# STM32F030_-_VGA_bare_-_v6.net
KiCad netlist of a schematic drawn in EAGLE
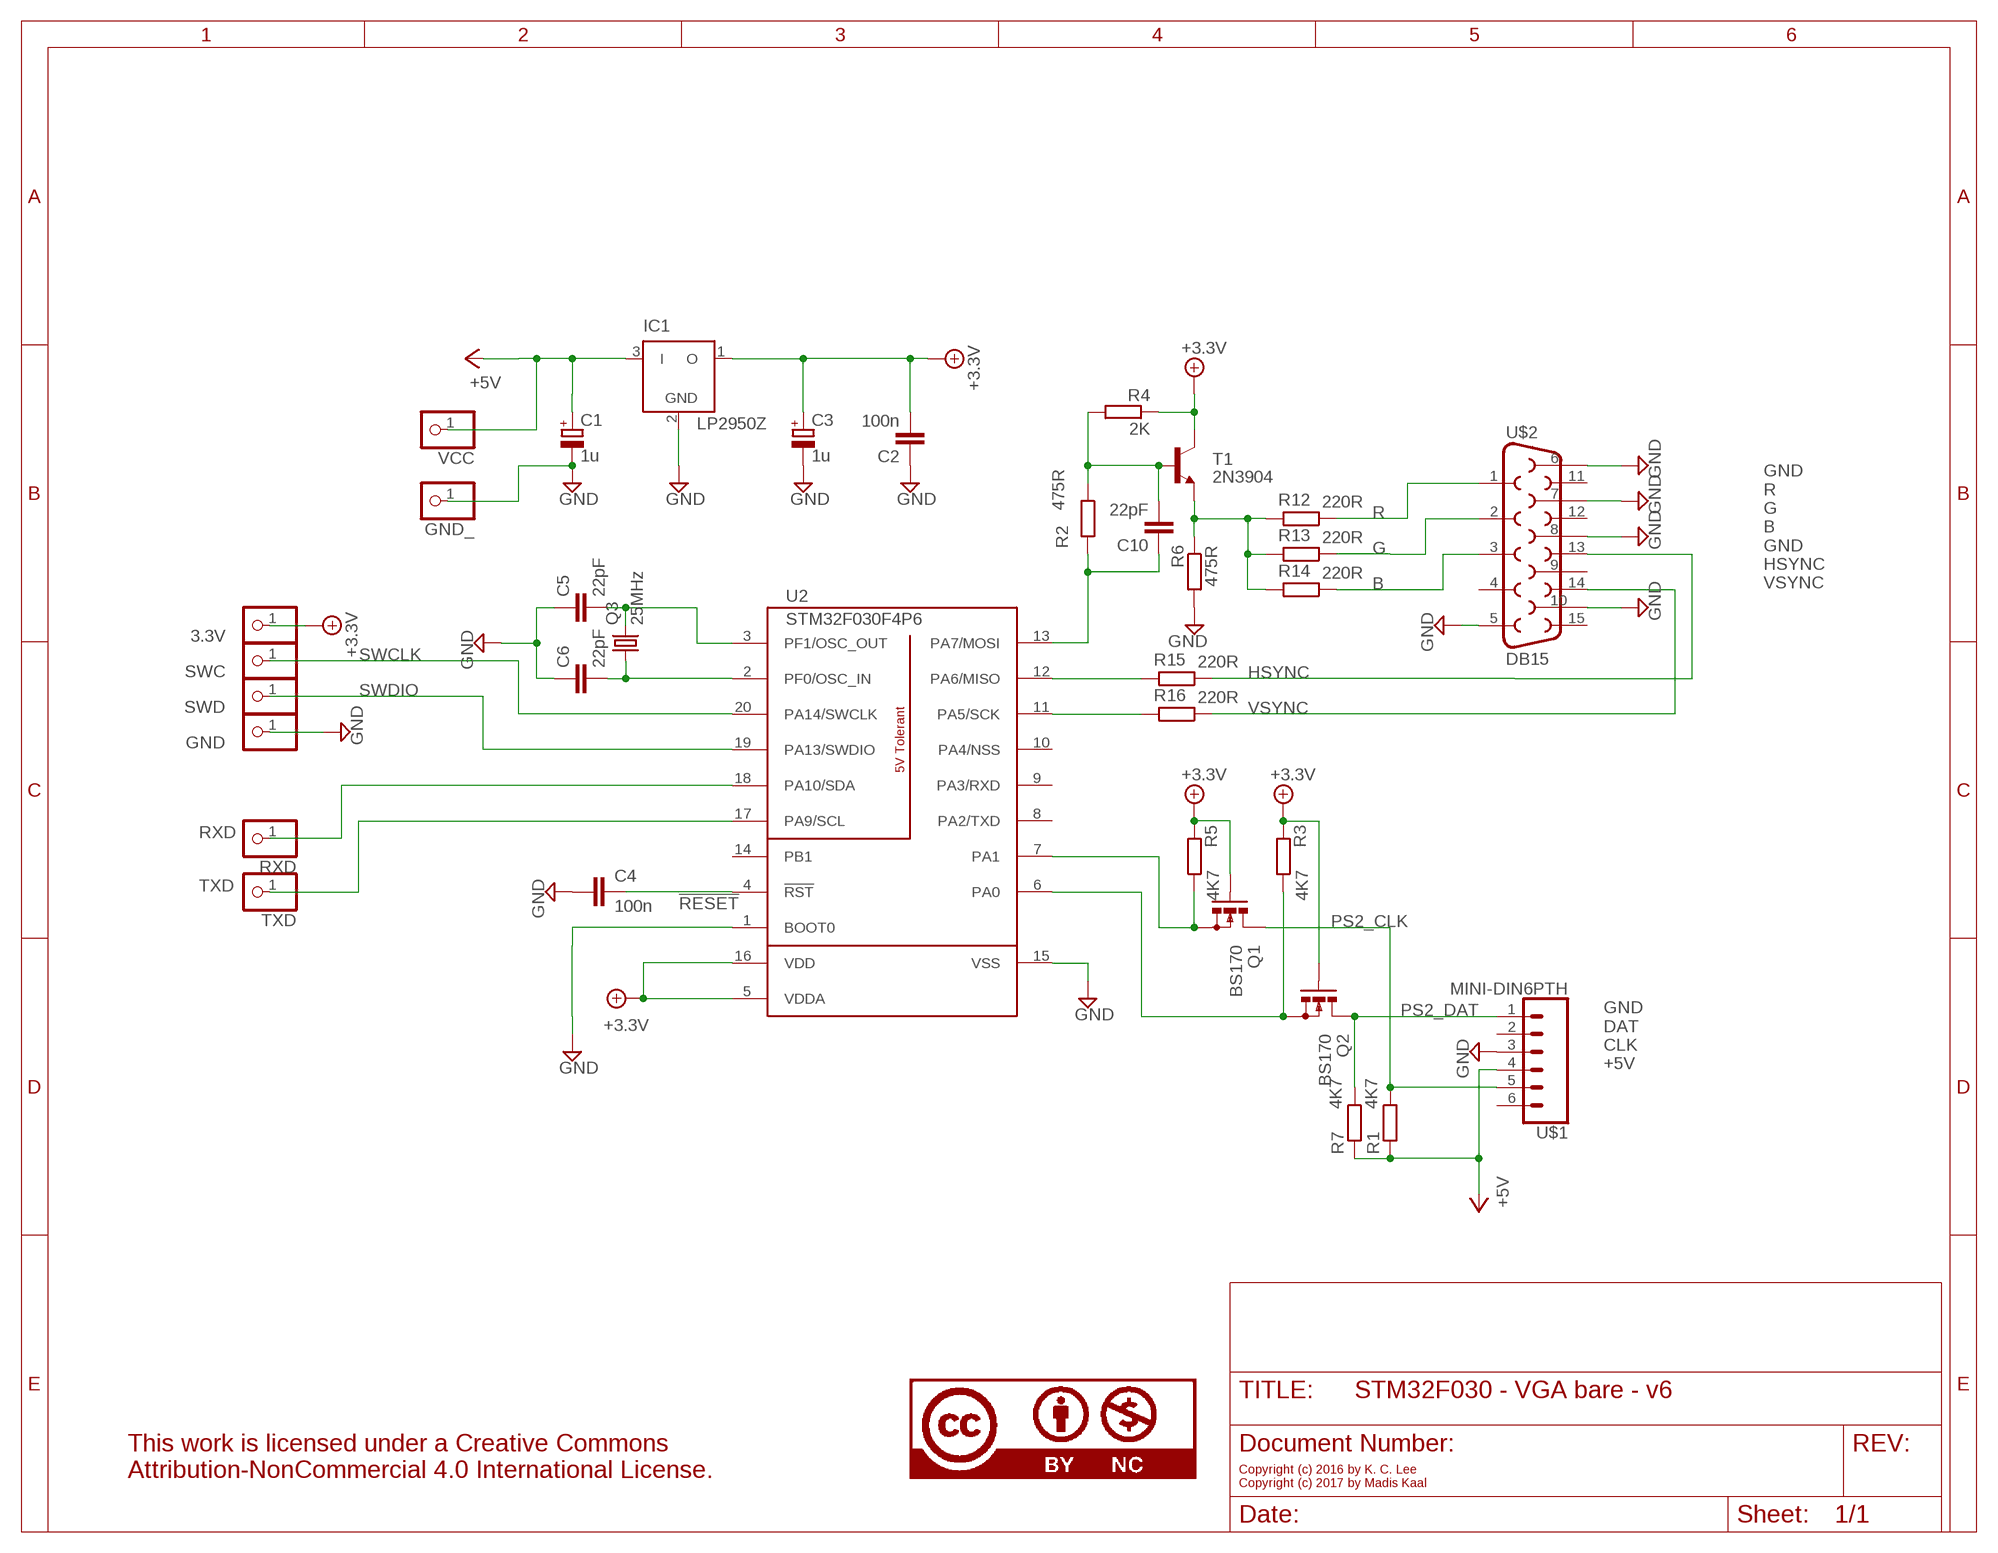
[diagram p0: schematic, sheet 1]

(export (version "E")
  (design (tool "Eeschema 10.0.6"))
  (components
    (comp (ref "3.3V")
      (value "PINHD-1X1")
      (footprint "eagle-import:1X01")
      (libsource (lib "eagle-import") (part "PINHD-1X1"))
    )
    (comp (ref "C1")
      (value "1u")
      (footprint "eagle-import:E2,5-5")
      (libsource (lib "eagle-import") (part "CPOL-EUE2.5-5"))
    )
    (comp (ref "C2")
      (value "100n")
      (footprint "eagle-import:C025-025X050")
      (fields (field (name "PARTNO") "0.1UF, 0603"))
      (libsource (lib "eagle-import") (part "C-EU025-025X050"))
    )
    (comp (ref "C3")
      (value "1u")
      (footprint "eagle-import:E2,5-5")
      (libsource (lib "eagle-import") (part "CPOL-EUE2.5-5"))
    )
    (comp (ref "C4")
      (value "100n")
      (footprint "eagle-import:C025-025X050")
      (fields (field (name "PARTNO") "0.1UF, 0603"))
      (libsource (lib "eagle-import") (part "C-EU025-025X050"))
    )
    (comp (ref "C5")
      (value "22pF")
      (footprint "eagle-import:C025-025X050")
      (fields (field (name "PARTNO") "22PF, 0603"))
      (libsource (lib "eagle-import") (part "C-EU025-025X050"))
    )
    (comp (ref "C6")
      (value "22pF")
      (footprint "eagle-import:C025-025X050")
      (fields (field (name "PARTNO") "22PF, 0603"))
      (libsource (lib "eagle-import") (part "C-EU025-025X050"))
    )
    (comp (ref "C10")
      (value "22pF")
      (footprint "eagle-import:C025-025X050")
      (fields (field (name "PARTNO") "22PF, 0603"))
      (libsource (lib "eagle-import") (part "C-EU025-025X050"))
    )
    (comp (ref "GND")
      (value "PINHD-1X1")
      (footprint "eagle-import:1X01")
      (libsource (lib "eagle-import") (part "PINHD-1X1"))
    )
    (comp (ref "GND_")
      (value "PINHD-1X1")
      (footprint "eagle-import:1X01")
      (libsource (lib "eagle-import") (part "PINHD-1X1"))
    )
    (comp (ref "IC1")
      (value "LP2950Z")
      (footprint "eagle-import:TO92")
      (libsource (lib "eagle-import") (part "LP2950Z"))
    )
    (comp (ref "LICENSE")
      (value "CC-BY-NC")
      (footprint "eagle-import:CC-BY-NC-75")
      (fields (field (name "PARTNO") "LICENSE"))
      (libsource (lib "eagle-import") (part "CC-BY-NC75%"))
    )
    (comp (ref "Q1")
      (value "BS170")
      (footprint "eagle-import:SOT54E")
      (libsource (lib "eagle-import") (part "BS170"))
    )
    (comp (ref "Q2")
      (value "BS170")
      (footprint "eagle-import:SOT54E")
      (libsource (lib "eagle-import") (part "BS170"))
    )
    (comp (ref "Q3")
      (value "25MHz")
      (footprint "eagle-import:HC49U-V")
      (libsource (lib "eagle-import") (part "CRYSTALHC49U-V"))
    )
    (comp (ref "R1")
      (value "4K7")
      (footprint "eagle-import:0204_7")
      (fields (field (name "PARTNO") "4K7, 0603"))
      (libsource (lib "eagle-import") (part "R-EU_0204/7"))
    )
    (comp (ref "R2")
      (value "475R")
      (footprint "eagle-import:0204_7")
      (fields (field (name "PARTNO") "475R, 0603"))
      (libsource (lib "eagle-import") (part "R-EU_0204/7"))
    )
    (comp (ref "R3")
      (value "4K7")
      (footprint "eagle-import:0204_7")
      (fields (field (name "PARTNO") "4K7, 0603"))
      (libsource (lib "eagle-import") (part "R-EU_0204/7"))
    )
    (comp (ref "R4")
      (value "2K")
      (footprint "eagle-import:0204_7")
      (fields (field (name "PARTNO") "2K, 0603"))
      (libsource (lib "eagle-import") (part "R-EU_0204/7"))
    )
    (comp (ref "R5")
      (value "4K7")
      (footprint "eagle-import:0204_7")
      (fields (field (name "PARTNO") "4K7, 0603"))
      (libsource (lib "eagle-import") (part "R-EU_0204/7"))
    )
    (comp (ref "R6")
      (value "475R")
      (footprint "eagle-import:0204_7")
      (fields (field (name "PARTNO") "475R, 0603"))
      (libsource (lib "eagle-import") (part "R-EU_0204/7"))
    )
    (comp (ref "R7")
      (value "4K7")
      (footprint "eagle-import:0204_7")
      (fields (field (name "PARTNO") "4K7, 0603"))
      (libsource (lib "eagle-import") (part "R-EU_0204/7"))
    )
    (comp (ref "R12")
      (value "220R")
      (footprint "eagle-import:0204_7")
      (libsource (lib "eagle-import") (part "R-EU_0204/7"))
    )
    (comp (ref "R13")
      (value "220R")
      (footprint "eagle-import:0204_7")
      (libsource (lib "eagle-import") (part "R-EU_0204/7"))
    )
    (comp (ref "R14")
      (value "220R")
      (footprint "eagle-import:0204_7")
      (libsource (lib "eagle-import") (part "R-EU_0204/7"))
    )
    (comp (ref "R15")
      (value "220R")
      (footprint "eagle-import:0204_7")
      (libsource (lib "eagle-import") (part "R-EU_0204/7"))
    )
    (comp (ref "R16")
      (value "220R")
      (footprint "eagle-import:0204_7")
      (libsource (lib "eagle-import") (part "R-EU_0204/7"))
    )
    (comp (ref "RXD")
      (value "PINHD-1X1")
      (footprint "eagle-import:1X01")
      (libsource (lib "eagle-import") (part "PINHD-1X1"))
    )
    (comp (ref "SWC")
      (value "PINHD-1X1")
      (footprint "eagle-import:1X01")
      (libsource (lib "eagle-import") (part "PINHD-1X1"))
    )
    (comp (ref "SWD")
      (value "PINHD-1X1")
      (footprint "eagle-import:1X01")
      (libsource (lib "eagle-import") (part "PINHD-1X1"))
    )
    (comp (ref "T1")
      (value "2N3904")
      (footprint "eagle-import:TO92")
      (libsource (lib "eagle-import") (part "2N3904"))
    )
    (comp (ref "TXD")
      (value "PINHD-1X1")
      (footprint "eagle-import:1X01")
      (libsource (lib "eagle-import") (part "PINHD-1X1"))
    )
    (comp (ref "U$1")
      (value "MINI-DIN6PTH")
      (footprint "eagle-import:MINI-DIN6")
      (libsource (lib "eagle-import") (part "MINI-DIN6PTH"))
    )
    (comp (ref "U$2")
      (value "DB15")
      (footprint "eagle-import:DB15")
      (libsource (lib "eagle-import") (part "DB15"))
    )
    (comp (ref "U2")
      (value "STM32F030F4P6")
      (footprint "eagle-import:TSSOP20")
      (libsource (lib "eagle-import") (part "STM32F030F4P6"))
    )
    (comp (ref "VCC")
      (value "PINHD-1X1")
      (footprint "eagle-import:1X01")
      (libsource (lib "eagle-import") (part "PINHD-1X1"))
    )
  )
  (nets
    (net (code "1") (name "+3.3V") (class "Default")
      (node (ref "3.3V") (pin "1") (pinfunction "1_1") (pintype "passive"))
      (node (ref "C2") (pin "2") (pinfunction "2_2") (pintype "passive"))
      (node (ref "C3") (pin "+") (pinfunction "+_+") (pintype "passive"))
      (node (ref "IC1") (pin "1") (pinfunction "O_1") (pintype "input"))
      (node (ref "Q1") (pin "G") (pinfunction "G_G") (pintype "passive"))
      (node (ref "Q2") (pin "G") (pinfunction "G_G") (pintype "passive"))
      (node (ref "R3") (pin "2") (pinfunction "2_2") (pintype "passive"))
      (node (ref "R4") (pin "1") (pinfunction "1_1") (pintype "passive"))
      (node (ref "R5") (pin "2") (pinfunction "2_2") (pintype "passive"))
      (node (ref "T1") (pin "1") (pinfunction "C_1") (pintype "passive"))
      (node (ref "U2") (pin "16") (pinfunction "VDD_16") (pintype "input"))
      (node (ref "U2") (pin "5") (pinfunction "VDDA_5") (pintype "input"))
    )
    (net (code "2") (name "+5V") (class "Default")
      (node (ref "C1") (pin "+") (pinfunction "+_+") (pintype "passive"))
      (node (ref "IC1") (pin "3") (pinfunction "I_3") (pintype "input"))
      (node (ref "R1") (pin "2") (pinfunction "2_2") (pintype "passive"))
      (node (ref "R7") (pin "2") (pinfunction "2_2") (pintype "passive"))
      (node (ref "U$1") (pin "4") (pinfunction "4_4") (pintype "passive"))
      (node (ref "VCC") (pin "1") (pinfunction "1_1") (pintype "passive"))
    )
    (net (code "3") (name "/B") (class "Default")
      (node (ref "R14") (pin "1") (pinfunction "1_1") (pintype "passive"))
      (node (ref "U$2") (pin "3") (pinfunction "3_3") (pintype "passive"))
    )
    (net (code "4") (name "/G") (class "Default")
      (node (ref "R13") (pin "1") (pinfunction "1_1") (pintype "passive"))
      (node (ref "U$2") (pin "2") (pinfunction "2_2") (pintype "passive"))
    )
    (net (code "5") (name "/HSYNC") (class "Default")
      (node (ref "R15") (pin "1") (pinfunction "1_1") (pintype "passive"))
      (node (ref "U$2") (pin "13") (pinfunction "13_13") (pintype "passive"))
    )
    (net (code "6") (name "/PS2_CLK") (class "Default")
      (node (ref "Q1") (pin "D") (pinfunction "D_D") (pintype "passive"))
      (node (ref "R1") (pin "1") (pinfunction "1_1") (pintype "passive"))
      (node (ref "U$1") (pin "5") (pinfunction "5_5") (pintype "passive"))
    )
    (net (code "7") (name "/PS2_DAT") (class "Default")
      (node (ref "Q2") (pin "D") (pinfunction "D_D") (pintype "passive"))
      (node (ref "R7") (pin "1") (pinfunction "1_1") (pintype "passive"))
      (node (ref "U$1") (pin "1") (pinfunction "1_1") (pintype "passive"))
    )
    (net (code "8") (name "/R") (class "Default")
      (node (ref "R12") (pin "1") (pinfunction "1_1") (pintype "passive"))
      (node (ref "U$2") (pin "1") (pinfunction "1_1") (pintype "passive"))
    )
    (net (code "9") (name "/RXD") (class "Default")
      (node (ref "RXD") (pin "1") (pinfunction "1_1") (pintype "passive"))
      (node (ref "U2") (pin "18") (pinfunction "PA10/SDA_18") (pintype "bidirectional"))
    )
    (net (code "10") (name "/SWCLK") (class "Default")
      (node (ref "SWC") (pin "1") (pinfunction "1_1") (pintype "passive"))
      (node (ref "U2") (pin "20") (pinfunction "PA14/SWCLK_20") (pintype "bidirectional"))
    )
    (net (code "11") (name "/SWDIO") (class "Default")
      (node (ref "SWD") (pin "1") (pinfunction "1_1") (pintype "passive"))
      (node (ref "U2") (pin "19") (pinfunction "PA13/SWDIO_19") (pintype "bidirectional"))
    )
    (net (code "12") (name "/TXD") (class "Default")
      (node (ref "TXD") (pin "1") (pinfunction "1_1") (pintype "passive"))
      (node (ref "U2") (pin "17") (pinfunction "PA9/SCL_17") (pintype "bidirectional"))
    )
    (net (code "13") (name "/VSYNC") (class "Default")
      (node (ref "R16") (pin "1") (pinfunction "1_1") (pintype "passive"))
      (node (ref "U$2") (pin "14") (pinfunction "14_14") (pintype "passive"))
    )
    (net (code "14") (name "/~{RESET}") (class "Default")
      (node (ref "C4") (pin "1") (pinfunction "1_1") (pintype "passive"))
      (node (ref "U2") (pin "4") (pinfunction "~{RST}_4") (pintype "input"))
    )
    (net (code "15") (name "GND") (class "Default")
      (node (ref "C1") (pin "-") (pinfunction "-_-") (pintype "passive"))
      (node (ref "C2") (pin "1") (pinfunction "1_1") (pintype "passive"))
      (node (ref "C3") (pin "-") (pinfunction "-_-") (pintype "passive"))
      (node (ref "C4") (pin "2") (pinfunction "2_2") (pintype "passive"))
      (node (ref "C5") (pin "1") (pinfunction "1_1") (pintype "passive"))
      (node (ref "C6") (pin "1") (pinfunction "1_1") (pintype "passive"))
      (node (ref "GND") (pin "1") (pinfunction "1_1") (pintype "passive"))
      (node (ref "GND_") (pin "1") (pinfunction "1_1") (pintype "passive"))
      (node (ref "IC1") (pin "2") (pinfunction "GND_2") (pintype "power_in"))
      (node (ref "R6") (pin "2") (pinfunction "2_2") (pintype "passive"))
      (node (ref "U$1") (pin "3") (pinfunction "3_3") (pintype "passive"))
      (node (ref "U$2") (pin "10") (pinfunction "10_10") (pintype "passive"))
      (node (ref "U$2") (pin "5") (pinfunction "5_5") (pintype "passive"))
      (node (ref "U$2") (pin "6") (pinfunction "6_6") (pintype "passive"))
      (node (ref "U$2") (pin "7") (pinfunction "7_7") (pintype "passive"))
      (node (ref "U$2") (pin "8") (pinfunction "8_8") (pintype "passive"))
      (node (ref "U2") (pin "1") (pinfunction "BOOT0_1") (pintype "input"))
      (node (ref "U2") (pin "15") (pinfunction "VSS_15") (pintype "input"))
    )
    (net (code "16") (name "Net-(T1-B)") (class "Default")
      (node (ref "C10") (pin "2") (pinfunction "2_2") (pintype "passive"))
      (node (ref "R2") (pin "1") (pinfunction "1_1") (pintype "passive"))
      (node (ref "R4") (pin "2") (pinfunction "2_2") (pintype "passive"))
      (node (ref "T1") (pin "2") (pinfunction "B_2") (pintype "passive"))
    )
    (net (code "17") (name "Net-(T1-E)") (class "Default")
      (node (ref "R12") (pin "2") (pinfunction "2_2") (pintype "passive"))
      (node (ref "R13") (pin "2") (pinfunction "2_2") (pintype "passive"))
      (node (ref "R14") (pin "2") (pinfunction "2_2") (pintype "passive"))
      (node (ref "R6") (pin "1") (pinfunction "1_1") (pintype "passive"))
      (node (ref "T1") (pin "3") (pinfunction "E_3") (pintype "passive"))
    )
    (net (code "18") (name "Net-(U2-PA0)") (class "Default")
      (node (ref "Q2") (pin "S") (pinfunction "S_S") (pintype "passive"))
      (node (ref "R3") (pin "1") (pinfunction "1_1") (pintype "passive"))
      (node (ref "U2") (pin "6") (pinfunction "PA0_6") (pintype "bidirectional"))
    )
    (net (code "19") (name "Net-(U2-PA1)") (class "Default")
      (node (ref "Q1") (pin "S") (pinfunction "S_S") (pintype "passive"))
      (node (ref "R5") (pin "1") (pinfunction "1_1") (pintype "passive"))
      (node (ref "U2") (pin "7") (pinfunction "PA1_7") (pintype "bidirectional"))
    )
    (net (code "20") (name "Net-(U2-PA5{slash}SCK)") (class "Default")
      (node (ref "R16") (pin "2") (pinfunction "2_2") (pintype "passive"))
      (node (ref "U2") (pin "11") (pinfunction "PA5/SCK_11") (pintype "bidirectional"))
    )
    (net (code "21") (name "Net-(U2-PA6{slash}MISO)") (class "Default")
      (node (ref "R15") (pin "2") (pinfunction "2_2") (pintype "passive"))
      (node (ref "U2") (pin "12") (pinfunction "PA6/MISO_12") (pintype "bidirectional"))
    )
    (net (code "22") (name "Net-(U2-PA7{slash}MOSI)") (class "Default")
      (node (ref "C10") (pin "1") (pinfunction "1_1") (pintype "passive"))
      (node (ref "R2") (pin "2") (pinfunction "2_2") (pintype "passive"))
      (node (ref "U2") (pin "13") (pinfunction "PA7/MOSI_13") (pintype "bidirectional"))
    )
    (net (code "23") (name "Net-(U2-PF0{slash}OSC_IN)") (class "Default")
      (node (ref "C6") (pin "2") (pinfunction "2_2") (pintype "passive"))
      (node (ref "Q3") (pin "1") (pinfunction "1_1") (pintype "passive"))
      (node (ref "U2") (pin "2") (pinfunction "PF0/OSC_IN_2") (pintype "input"))
    )
    (net (code "24") (name "Net-(U2-PF1{slash}OSC_OUT)") (class "Default")
      (node (ref "C5") (pin "2") (pinfunction "2_2") (pintype "passive"))
      (node (ref "Q3") (pin "2") (pinfunction "2_2") (pintype "passive"))
      (node (ref "U2") (pin "3") (pinfunction "PF1/OSC_OUT_3") (pintype "output"))
    )
    (net (code "25") (name "unconnected-(U$1-Pad2)") (class "Default")
      (node (ref "U$1") (pin "2") (pinfunction "2_2") (pintype "passive"))
    )
    (net (code "26") (name "unconnected-(U$1-Pad6)") (class "Default")
      (node (ref "U$1") (pin "6") (pinfunction "6_6") (pintype "passive"))
    )
    (net (code "27") (name "unconnected-(U$2-Pad4)") (class "Default")
      (node (ref "U$2") (pin "4") (pinfunction "4_4") (pintype "passive"))
    )
    (net (code "28") (name "unconnected-(U$2-Pad9)") (class "Default")
      (node (ref "U$2") (pin "9") (pinfunction "9_9") (pintype "passive"))
    )
    (net (code "29") (name "unconnected-(U$2-Pad11)") (class "Default")
      (node (ref "U$2") (pin "11") (pinfunction "11_11") (pintype "passive"))
    )
    (net (code "30") (name "unconnected-(U$2-Pad12)") (class "Default")
      (node (ref "U$2") (pin "12") (pinfunction "12_12") (pintype "passive"))
    )
    (net (code "31") (name "unconnected-(U$2-Pad15)") (class "Default")
      (node (ref "U$2") (pin "15") (pinfunction "15_15") (pintype "passive"))
    )
    (net (code "32") (name "unconnected-(U2-PA2{slash}TXD-Pad8)") (class "Default")
      (node (ref "U2") (pin "8") (pinfunction "PA2/TXD_8") (pintype "bidirectional"))
    )
    (net (code "33") (name "unconnected-(U2-PA3{slash}RXD-Pad9)") (class "Default")
      (node (ref "U2") (pin "9") (pinfunction "PA3/RXD_9") (pintype "bidirectional"))
    )
    (net (code "34") (name "unconnected-(U2-PA4{slash}NSS-Pad10)") (class "Default")
      (node (ref "U2") (pin "10") (pinfunction "PA4/NSS_10") (pintype "bidirectional"))
    )
    (net (code "35") (name "unconnected-(U2-PB1-Pad14)") (class "Default")
      (node (ref "U2") (pin "14") (pinfunction "PB1_14") (pintype "bidirectional"))
    )
  )
)
